# tyraka2_0.net
KiCad netlist of a schematic drawn in EAGLE
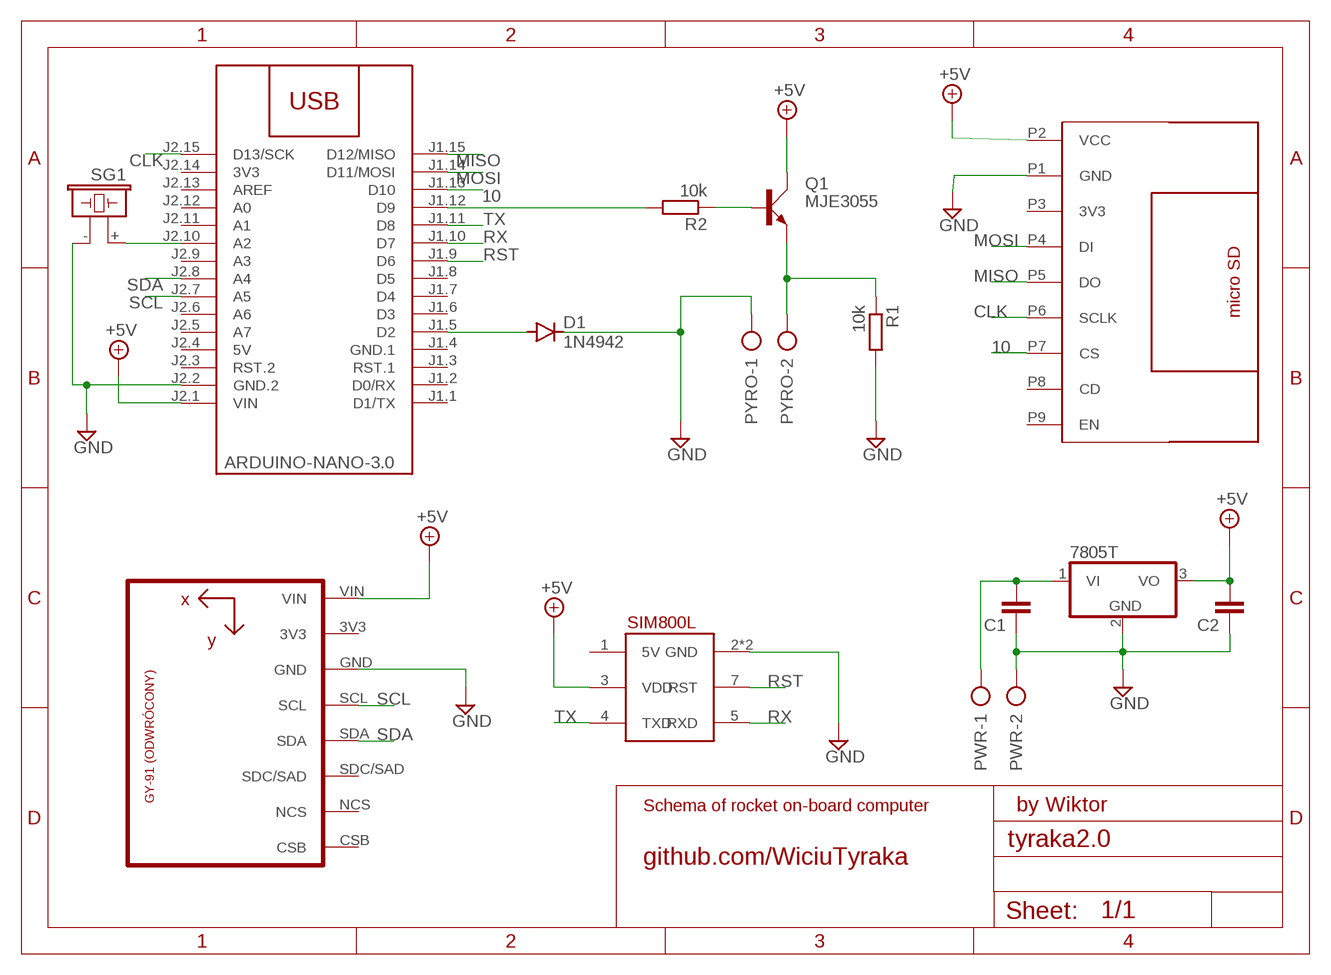
[diagram p0: schematic, sheet 1]

(export (version "E")
  (design (tool "Eeschema 10.0.6"))
  (components
    (comp (ref "C1")
      (value "C2.5/4")
      (footprint "eagle-import:C2.5-4")
      (libsource (lib "eagle-import") (part "C2.5/4"))
    )
    (comp (ref "C2")
      (value "C2.5/4")
      (footprint "eagle-import:C2.5-4")
      (libsource (lib "eagle-import") (part "C2.5/4"))
    )
    (comp (ref "D1")
      (value "1N4942")
      (footprint "eagle-import:DO41-10")
      (libsource (lib "eagle-import") (part "1N4942"))
    )
    (comp (ref "IC2")
      (value "7805T")
      (footprint "eagle-import:TO220H")
      (libsource (lib "eagle-import") (part "78T05"))
    )
    (comp (ref "M1")
      (value "ARDUINO-NANO-3.0")
      (footprint "eagle-import:ARDUINO-NANO-3.0")
      (libsource (lib "eagle-import") (part "ARDUINO-NANO-3.0"))
    )
    (comp (ref "PWR")
      (value "AK500/2")
      (footprint "eagle-import:AK500_2")
      (libsource (lib "eagle-import") (part "AK500/2"))
    )
    (comp (ref "PYRO")
      (value "AK500/2")
      (footprint "eagle-import:AK500_2")
      (libsource (lib "eagle-import") (part "AK500/2"))
    )
    (comp (ref "Q1")
      (value "MJE3055")
      (footprint "eagle-import:TO220AV")
      (libsource (lib "eagle-import") (part "MJE3055"))
    )
    (comp (ref "R1")
      (value "10k")
      (footprint "eagle-import:0204_5")
      (libsource (lib "eagle-import") (part "R-EU_0204/5"))
    )
    (comp (ref "R2")
      (value "10k")
      (footprint "eagle-import:0204_5")
      (libsource (lib "eagle-import") (part "R-EU_0204/5"))
    )
    (comp (ref "SD1")
      (value "MICRO_SD")
      (footprint "eagle-import:MICRO_SD")
      (libsource (lib "eagle-import") (part "MICRO_SD"))
    )
    (comp (ref "SG1")
      (value "F/CM12P")
      (footprint "eagle-import:F_CM12P")
      (libsource (lib "eagle-import") (part "F/CM12P"))
    )
    (comp (ref "U$1")
      (value "SIM800L")
      (footprint "eagle-import:SIP")
      (libsource (lib "eagle-import") (part "SIM800L"))
    )
    (comp (ref "U1")
      (value "GY-521MPU6050")
      (footprint "eagle-import:GY-521")
      (libsource (lib "eagle-import") (part "GY-521MPU6050"))
    )
  )
  (nets
    (net (code "1") (name "+5V") (class "Default")
      (node (ref "C2") (pin "2") (pinfunction "2_2") (pintype "passive"))
      (node (ref "IC2") (pin "3") (pinfunction "VO_3") (pintype "passive"))
      (node (ref "M1") (pin "J2.1") (pinfunction "VIN_J2.1") (pintype "power_in"))
      (node (ref "Q1") (pin "C") (pinfunction "C_C") (pintype "passive"))
      (node (ref "SD1") (pin "P2") (pinfunction "VCC_P2") (pintype "power_in"))
      (node (ref "U$1") (pin "3") (pinfunction "VDD_3") (pintype "bidirectional"))
      (node (ref "U1") (pin "VIN") (pinfunction "VIN_VIN") (pintype "bidirectional"))
    )
    (net (code "2") (name "/3V3") (class "Default")
      (node (ref "M1") (pin "J2.14") (pinfunction "3V3_J2.14") (pintype "power_in"))
    )
    (net (code "3") (name "/5V") (class "Default")
      (node (ref "M1") (pin "J2.4") (pinfunction "5V_J2.4") (pintype "power_in"))
    )
    (net (code "4") (name "/10") (class "Default")
      (node (ref "M1") (pin "J1.13") (pinfunction "D10_J1.13") (pintype "bidirectional"))
      (node (ref "SD1") (pin "P7") (pinfunction "CS_P7") (pintype "bidirectional"))
    )
    (net (code "5") (name "/CLK") (class "Default")
      (node (ref "M1") (pin "J2.15") (pinfunction "D13/SCK_J2.15") (pintype "bidirectional"))
      (node (ref "SD1") (pin "P6") (pinfunction "SCLK_P6") (pintype "bidirectional"))
    )
    (net (code "6") (name "/GND.1") (class "Default")
      (node (ref "M1") (pin "J1.4") (pinfunction "GND.1_J1.4") (pintype "power_in"))
    )
    (net (code "7") (name "/MISO") (class "Default")
      (node (ref "M1") (pin "J1.15") (pinfunction "D12/MISO_J1.15") (pintype "bidirectional"))
      (node (ref "SD1") (pin "P5") (pinfunction "DO_P5") (pintype "bidirectional"))
    )
    (net (code "8") (name "/MOSI") (class "Default")
      (node (ref "M1") (pin "J1.14") (pinfunction "D11/MOSI_J1.14") (pintype "bidirectional"))
      (node (ref "SD1") (pin "P4") (pinfunction "DI_P4") (pintype "bidirectional"))
    )
    (net (code "9") (name "/RST") (class "Default")
      (node (ref "M1") (pin "J1.9") (pinfunction "D6_J1.9") (pintype "bidirectional"))
      (node (ref "U$1") (pin "7") (pinfunction "RST_7") (pintype "bidirectional"))
    )
    (net (code "10") (name "/RX") (class "Default")
      (node (ref "M1") (pin "J1.10") (pinfunction "D7_J1.10") (pintype "bidirectional"))
      (node (ref "U$1") (pin "5") (pinfunction "RXD_5") (pintype "bidirectional"))
    )
    (net (code "11") (name "/SCL") (class "Default")
      (node (ref "M1") (pin "J2.7") (pinfunction "A5_J2.7") (pintype "bidirectional"))
      (node (ref "U1") (pin "SCL") (pinfunction "SCL_SCL") (pintype "bidirectional"))
    )
    (net (code "12") (name "/SDA") (class "Default")
      (node (ref "M1") (pin "J2.8") (pinfunction "A4_J2.8") (pintype "bidirectional"))
      (node (ref "U1") (pin "SDA") (pinfunction "SDA_SDA") (pintype "bidirectional"))
    )
    (net (code "13") (name "/TX") (class "Default")
      (node (ref "M1") (pin "J1.11") (pinfunction "D8_J1.11") (pintype "bidirectional"))
      (node (ref "U$1") (pin "4") (pinfunction "TXD_4") (pintype "bidirectional"))
    )
    (net (code "14") (name "GND") (class "Default")
      (node (ref "C1") (pin "1") (pinfunction "1_1") (pintype "passive"))
      (node (ref "C2") (pin "1") (pinfunction "1_1") (pintype "passive"))
      (node (ref "D1") (pin "C") (pinfunction "C_C") (pintype "passive"))
      (node (ref "IC2") (pin "2") (pinfunction "GND_2") (pintype "passive"))
      (node (ref "M1") (pin "J2.2") (pinfunction "GND.2_J2.2") (pintype "power_in"))
      (node (ref "PWR") (pin "2") (pinfunction "KL_2") (pintype "passive"))
      (node (ref "PYRO") (pin "1") (pinfunction "KL_1") (pintype "passive"))
      (node (ref "R1") (pin "2") (pinfunction "2_2") (pintype "passive"))
      (node (ref "SD1") (pin "P1") (pinfunction "GND_P1") (pintype "power_in"))
      (node (ref "SG1") (pin "-") (pinfunction "2_-") (pintype "passive"))
      (node (ref "U$1") (pin "2") (pinfunction "GND_2") (pintype "bidirectional"))
      (node (ref "U$1") (pin "6") (pinfunction "GND_6") (pintype "bidirectional"))
      (node (ref "U1") (pin "GND") (pinfunction "GND_GND") (pintype "bidirectional"))
    )
    (net (code "15") (name "Net-(IC2-VI)") (class "Default")
      (node (ref "C1") (pin "2") (pinfunction "2_2") (pintype "passive"))
      (node (ref "IC2") (pin "1") (pinfunction "VI_1") (pintype "input"))
      (node (ref "PWR") (pin "1") (pinfunction "KL_1") (pintype "passive"))
    )
    (net (code "16") (name "Net-(M1-A2)") (class "Default")
      (node (ref "M1") (pin "J2.10") (pinfunction "A2_J2.10") (pintype "bidirectional"))
      (node (ref "SG1") (pin "+") (pinfunction "1_+") (pintype "passive"))
    )
    (net (code "17") (name "Net-(M1-D2)") (class "Default")
      (node (ref "D1") (pin "A") (pinfunction "A_A") (pintype "passive"))
      (node (ref "M1") (pin "J1.5") (pinfunction "D2_J1.5") (pintype "bidirectional"))
    )
    (net (code "18") (name "Net-(M1-D9)") (class "Default")
      (node (ref "M1") (pin "J1.12") (pinfunction "D9_J1.12") (pintype "bidirectional"))
      (node (ref "R2") (pin "2") (pinfunction "2_2") (pintype "passive"))
    )
    (net (code "19") (name "Net-(PYROB-KL)") (class "Default")
      (node (ref "PYRO") (pin "2") (pinfunction "KL_2") (pintype "passive"))
      (node (ref "Q1") (pin "E") (pinfunction "E_E") (pintype "passive"))
      (node (ref "R1") (pin "1") (pinfunction "1_1") (pintype "passive"))
    )
    (net (code "20") (name "Net-(Q1-PadB)") (class "Default")
      (node (ref "Q1") (pin "B") (pinfunction "B_B") (pintype "passive"))
      (node (ref "R2") (pin "1") (pinfunction "1_1") (pintype "passive"))
    )
    (net (code "21") (name "unconnected-(M1-A0-PadJ2.12)") (class "Default")
      (node (ref "M1") (pin "J2.12") (pinfunction "A0_J2.12") (pintype "bidirectional"))
    )
    (net (code "22") (name "unconnected-(M1-A1-PadJ2.11)") (class "Default")
      (node (ref "M1") (pin "J2.11") (pinfunction "A1_J2.11") (pintype "bidirectional"))
    )
    (net (code "23") (name "unconnected-(M1-A3-PadJ2.9)") (class "Default")
      (node (ref "M1") (pin "J2.9") (pinfunction "A3_J2.9") (pintype "bidirectional"))
    )
    (net (code "24") (name "unconnected-(M1-A6-PadJ2.6)") (class "Default")
      (node (ref "M1") (pin "J2.6") (pinfunction "A6_J2.6") (pintype "bidirectional"))
    )
    (net (code "25") (name "unconnected-(M1-A7-PadJ2.5)") (class "Default")
      (node (ref "M1") (pin "J2.5") (pinfunction "A7_J2.5") (pintype "bidirectional"))
    )
    (net (code "26") (name "unconnected-(M1-AREF-PadJ2.13)") (class "Default")
      (node (ref "M1") (pin "J2.13") (pinfunction "AREF_J2.13") (pintype "bidirectional"))
    )
    (net (code "27") (name "unconnected-(M1-D0{slash}RX-PadJ1.2)") (class "Default")
      (node (ref "M1") (pin "J1.2") (pinfunction "D0/RX_J1.2") (pintype "bidirectional"))
    )
    (net (code "28") (name "unconnected-(M1-D1{slash}TX-PadJ1.1)") (class "Default")
      (node (ref "M1") (pin "J1.1") (pinfunction "D1/TX_J1.1") (pintype "bidirectional"))
    )
    (net (code "29") (name "unconnected-(M1-D3-PadJ1.6)") (class "Default")
      (node (ref "M1") (pin "J1.6") (pinfunction "D3_J1.6") (pintype "bidirectional"))
    )
    (net (code "30") (name "unconnected-(M1-D4-PadJ1.7)") (class "Default")
      (node (ref "M1") (pin "J1.7") (pinfunction "D4_J1.7") (pintype "bidirectional"))
    )
    (net (code "31") (name "unconnected-(M1-D5-PadJ1.8)") (class "Default")
      (node (ref "M1") (pin "J1.8") (pinfunction "D5_J1.8") (pintype "bidirectional"))
    )
    (net (code "32") (name "unconnected-(M1-RST.1-PadJ1.3)") (class "Default")
      (node (ref "M1") (pin "J1.3") (pinfunction "RST.1_J1.3") (pintype "bidirectional"))
    )
    (net (code "33") (name "unconnected-(M1-RST.2-PadJ2.3)") (class "Default")
      (node (ref "M1") (pin "J2.3") (pinfunction "RST.2_J2.3") (pintype "bidirectional"))
    )
    (net (code "34") (name "unconnected-(SD1-3V3-PadP3)") (class "Default")
      (node (ref "SD1") (pin "P3") (pinfunction "3V3_P3") (pintype "bidirectional"))
    )
    (net (code "35") (name "unconnected-(SD1-CD-PadP8)") (class "Default")
      (node (ref "SD1") (pin "P8") (pinfunction "CD_P8") (pintype "bidirectional"))
    )
    (net (code "36") (name "unconnected-(SD1-EN-PadP9)") (class "Default")
      (node (ref "SD1") (pin "P9") (pinfunction "EN_P9") (pintype "bidirectional"))
    )
    (net (code "37") (name "unconnected-(U$1-5V-Pad1)") (class "Default")
      (node (ref "U$1") (pin "1") (pinfunction "5V_1") (pintype "bidirectional"))
    )
    (net (code "38") (name "unconnected-(U1-Pad3V3)") (class "Default")
      (node (ref "U1") (pin "3V3") (pinfunction "3V3_3V3") (pintype "bidirectional"))
    )
    (net (code "39") (name "unconnected-(U1-PadCSB)") (class "Default")
      (node (ref "U1") (pin "CSB") (pinfunction "CSB_CSB") (pintype "bidirectional"))
    )
    (net (code "40") (name "unconnected-(U1-PadNCS)") (class "Default")
      (node (ref "U1") (pin "NCS") (pinfunction "NCS_NCS") (pintype "bidirectional"))
    )
    (net (code "41") (name "unconnected-(U1-PadSDC{slash}SAD)") (class "Default")
      (node (ref "U1") (pin "SDC/SAD") (pinfunction "SDC/SAD_SDC/SAD") (pintype "bidirectional"))
    )
  )
)
